# as14120_x31_adc.net
KiCad netlist of a schematic drawn in Altium Designer
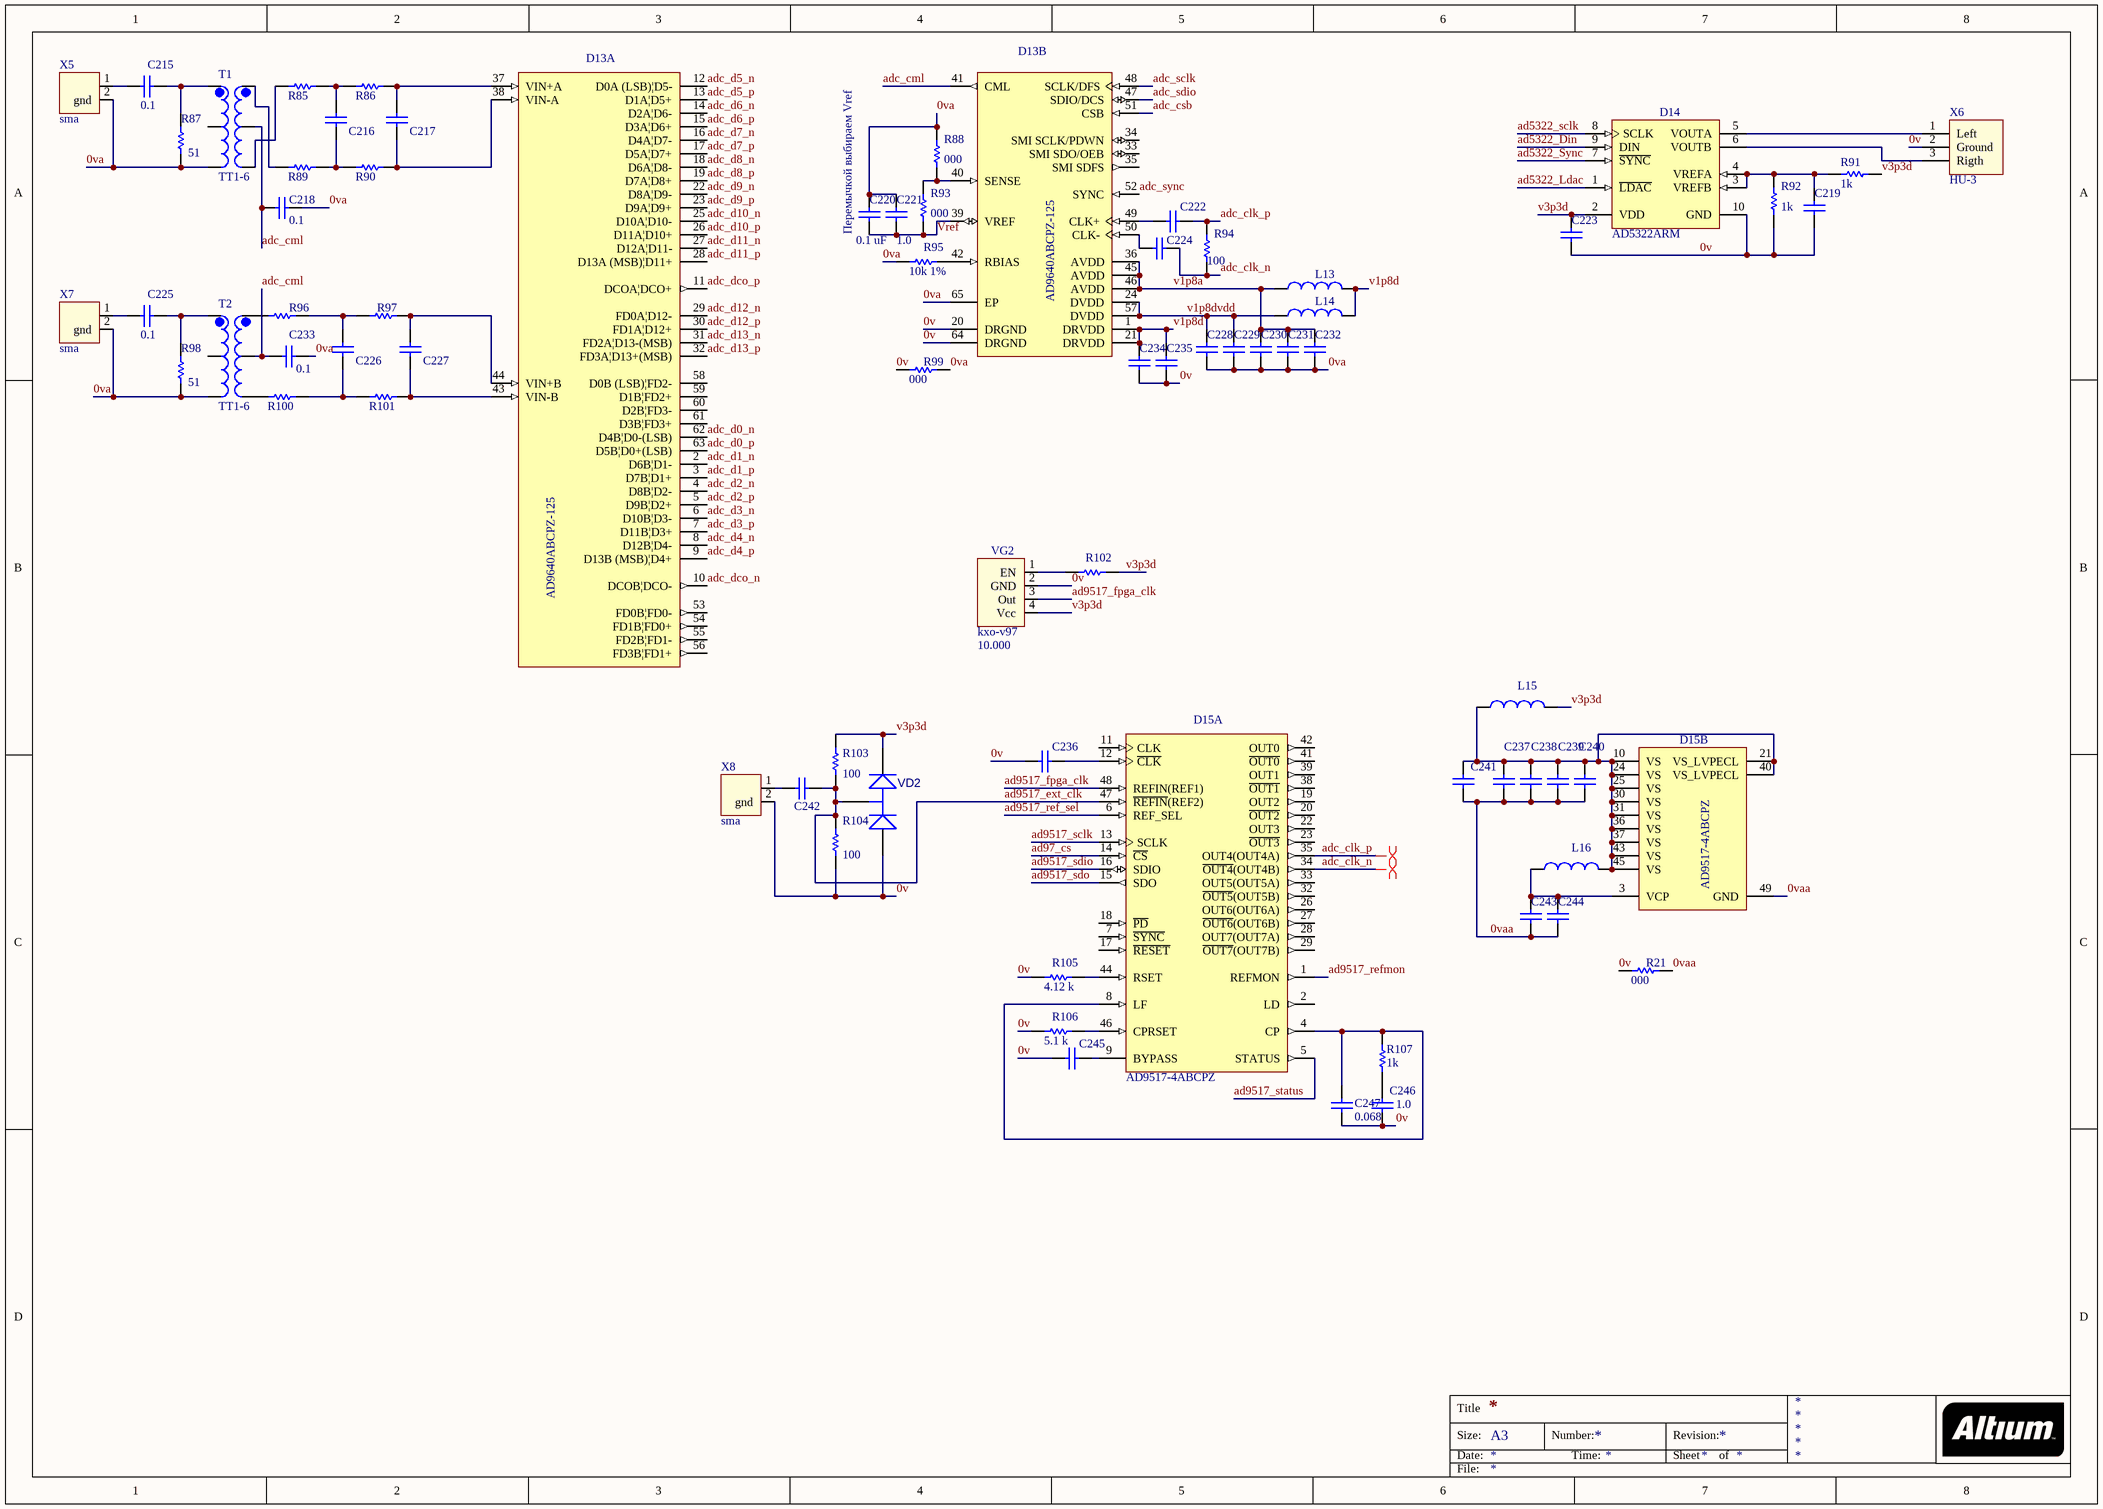
[diagram p0: as14120_x31_adc.SchDoc]

(export (version "E")
  (design (tool "Eeschema 10.0.6"))
  (components
    (comp (ref "C215")
      (value "0.1")
      (footprint "CAPC0402(1005)60_M")
      (description "CAP 1uF 10V ±20% 0402 (1005 Metric) Thickness 0.6mm SMD")
      (fields (field (name "TOLERANCE") "±20%") (field (name "Comment") "CAP 1uF 10V 0402(1005)"))
      (libsource (lib "as14120") (part "CAP_0402"))
    )
    (comp (ref "C216")
      (value "CAP 1uF 10V 0402(1005)")
      (footprint "CAPC0402(1005)60_M")
      (description "CAP 1uF 10V ±20% 0402 (1005 Metric) Thickness 0.6mm SMD")
      (fields (field (name "TOLERANCE") "±20%"))
      (libsource (lib "as14120") (part "CAP_0402"))
    )
    (comp (ref "C217")
      (value "CAP 1uF 10V 0402(1005)")
      (footprint "CAPC0402(1005)60_M")
      (description "CAP 1uF 10V ±20% 0402 (1005 Metric) Thickness 0.6mm SMD")
      (fields (field (name "TOLERANCE") "±20%"))
      (libsource (lib "as14120") (part "CAP_0402"))
    )
    (comp (ref "C218")
      (value "0.1")
      (footprint "CAPC0402(1005)60_M")
      (description "CAP 1uF 10V ±20% 0402 (1005 Metric) Thickness 0.6mm SMD")
      (fields (field (name "TOLERANCE") "±20%") (field (name "Comment") "CAP 1uF 10V 0402(1005)"))
      (libsource (lib "as14120") (part "CAP_0402"))
    )
    (comp (ref "C219")
      (value "CAP 1uF 10V 0402(1005)")
      (footprint "CAPC0402(1005)60_M")
      (description "CAP 1uF 10V ±20% 0402 (1005 Metric) Thickness 0.6mm SMD")
      (fields (field (name "TOLERANCE") "±20%"))
      (libsource (lib "as14120") (part "CAP_0402"))
    )
    (comp (ref "C220")
      (value "0.1 uF")
      (footprint "CAPC0402(1005)60_M")
      (description "CAP 1uF 10V ±20% 0402 (1005 Metric) Thickness 0.6mm SMD")
      (fields (field (name "TOLERANCE") "±20%") (field (name "Comment") "CAP 1uF 10V 0402(1005)"))
      (libsource (lib "as14120") (part "CAP_0402"))
    )
    (comp (ref "C221")
      (value "1.0")
      (footprint "CAPC0402(1005)60_M")
      (description "CAP 1uF 10V ±20% 0402 (1005 Metric) Thickness 0.6mm SMD")
      (fields (field (name "TOLERANCE") "±20%") (field (name "Comment") "CAP 1uF 10V 0402(1005)"))
      (libsource (lib "as14120") (part "CAP_0402"))
    )
    (comp (ref "C222")
      (value "CAP 1uF 10V 0402(1005)")
      (footprint "CAPC0402(1005)60_M")
      (description "CAP 1uF 10V ±20% 0402 (1005 Metric) Thickness 0.6mm SMD")
      (fields (field (name "TOLERANCE") "±20%"))
      (libsource (lib "as14120") (part "CAP_0402"))
    )
    (comp (ref "C223")
      (value "CAP 1uF 10V 0402(1005)")
      (footprint "CAPC0402(1005)60_M")
      (description "CAP 1uF 10V ±20% 0402 (1005 Metric) Thickness 0.6mm SMD")
      (fields (field (name "TOLERANCE") "±20%"))
      (libsource (lib "as14120") (part "CAP_0402"))
    )
    (comp (ref "C224")
      (value "CAP 1uF 10V 0402(1005)")
      (footprint "CAPC0402(1005)60_M")
      (description "CAP 1uF 10V ±20% 0402 (1005 Metric) Thickness 0.6mm SMD")
      (fields (field (name "TOLERANCE") "±20%"))
      (libsource (lib "as14120") (part "CAP_0402"))
    )
    (comp (ref "C225")
      (value "0.1")
      (footprint "CAPC0402(1005)60_M")
      (description "CAP 1uF 10V ±20% 0402 (1005 Metric) Thickness 0.6mm SMD")
      (fields (field (name "TOLERANCE") "±20%") (field (name "Comment") "CAP 1uF 10V 0402(1005)"))
      (libsource (lib "as14120") (part "CAP_0402"))
    )
    (comp (ref "C226")
      (value "CAP 1uF 10V 0402(1005)")
      (footprint "CAPC0402(1005)60_M")
      (description "CAP 1uF 10V ±20% 0402 (1005 Metric) Thickness 0.6mm SMD")
      (fields (field (name "TOLERANCE") "±20%"))
      (libsource (lib "as14120") (part "CAP_0402"))
    )
    (comp (ref "C227")
      (value "CAP 1uF 10V 0402(1005)")
      (footprint "CAPC0402(1005)60_M")
      (description "CAP 1uF 10V ±20% 0402 (1005 Metric) Thickness 0.6mm SMD")
      (fields (field (name "TOLERANCE") "±20%"))
      (libsource (lib "as14120") (part "CAP_0402"))
    )
    (comp (ref "C228")
      (value "CAP 1uF 10V 0402(1005)")
      (footprint "CAPC0402(1005)60_M")
      (description "CAP 1uF 10V ±20% 0402 (1005 Metric) Thickness 0.6mm SMD")
      (fields (field (name "TOLERANCE") "±20%"))
      (libsource (lib "as14120") (part "CAP_0402"))
    )
    (comp (ref "C229")
      (value "CAP 1uF 10V 0402(1005)")
      (footprint "CAPC0402(1005)60_M")
      (description "CAP 1uF 10V ±20% 0402 (1005 Metric) Thickness 0.6mm SMD")
      (fields (field (name "TOLERANCE") "±20%"))
      (libsource (lib "as14120") (part "CAP_0402"))
    )
    (comp (ref "C230")
      (value "CAP 1uF 10V 0402(1005)")
      (footprint "CAPC0402(1005)60_M")
      (description "CAP 1uF 10V ±20% 0402 (1005 Metric) Thickness 0.6mm SMD")
      (fields (field (name "TOLERANCE") "±20%"))
      (libsource (lib "as14120") (part "CAP_0402"))
    )
    (comp (ref "C231")
      (value "CAP 1uF 10V 0402(1005)")
      (footprint "CAPC0402(1005)60_M")
      (description "CAP 1uF 10V ±20% 0402 (1005 Metric) Thickness 0.6mm SMD")
      (fields (field (name "TOLERANCE") "±20%"))
      (libsource (lib "as14120") (part "CAP_0402"))
    )
    (comp (ref "C232")
      (value "CAP 1uF 10V 0402(1005)")
      (footprint "CAPC0402(1005)60_M")
      (description "CAP 1uF 10V ±20% 0402 (1005 Metric) Thickness 0.6mm SMD")
      (fields (field (name "TOLERANCE") "±20%"))
      (libsource (lib "as14120") (part "CAP_0402"))
    )
    (comp (ref "C233")
      (value "0.1")
      (footprint "CAPC0402(1005)60_M")
      (description "CAP 1uF 10V ±20% 0402 (1005 Metric) Thickness 0.6mm SMD")
      (fields (field (name "TOLERANCE") "±20%") (field (name "Comment") "CAP 1uF 10V 0402(1005)"))
      (libsource (lib "as14120") (part "CAP_0402"))
    )
    (comp (ref "C234")
      (value "CAP 1uF 10V 0402(1005)")
      (footprint "CAPC0402(1005)60_M")
      (description "CAP 1uF 10V ±20% 0402 (1005 Metric) Thickness 0.6mm SMD")
      (fields (field (name "TOLERANCE") "±20%"))
      (libsource (lib "as14120") (part "CAP_0402"))
    )
    (comp (ref "C235")
      (value "CAP 1uF 10V 0402(1005)")
      (footprint "CAPC0402(1005)60_M")
      (description "CAP 1uF 10V ±20% 0402 (1005 Metric) Thickness 0.6mm SMD")
      (fields (field (name "TOLERANCE") "±20%"))
      (libsource (lib "as14120") (part "CAP_0402"))
    )
    (comp (ref "C236")
      (value "CAP 1uF 10V 0402(1005)")
      (footprint "CAPC0402(1005)60_M")
      (description "CAP 1uF 10V ±20% 0402 (1005 Metric) Thickness 0.6mm SMD")
      (fields (field (name "TOLERANCE") "±20%"))
      (libsource (lib "as14120") (part "CAP_0402"))
    )
    (comp (ref "C237")
      (value "CAP 1uF 10V 0402(1005)")
      (footprint "CAPC0402(1005)60_M")
      (description "CAP 1uF 10V ±20% 0402 (1005 Metric) Thickness 0.6mm SMD")
      (fields (field (name "TOLERANCE") "±20%"))
      (libsource (lib "as14120") (part "CAP_0402"))
    )
    (comp (ref "C238")
      (value "CAP 1uF 10V 0402(1005)")
      (footprint "CAPC0402(1005)60_M")
      (description "CAP 1uF 10V ±20% 0402 (1005 Metric) Thickness 0.6mm SMD")
      (fields (field (name "TOLERANCE") "±20%"))
      (libsource (lib "as14120") (part "CAP_0402"))
    )
    (comp (ref "C239")
      (value "CAP 1uF 10V 0402(1005)")
      (footprint "CAPC0402(1005)60_M")
      (description "CAP 1uF 10V ±20% 0402 (1005 Metric) Thickness 0.6mm SMD")
      (fields (field (name "TOLERANCE") "±20%"))
      (libsource (lib "as14120") (part "CAP_0402"))
    )
    (comp (ref "C240")
      (value "CAP 1uF 10V 0402(1005)")
      (footprint "CAPC0402(1005)60_M")
      (description "CAP 1uF 10V ±20% 0402 (1005 Metric) Thickness 0.6mm SMD")
      (fields (field (name "TOLERANCE") "±20%"))
      (libsource (lib "as14120") (part "CAP_0402"))
    )
    (comp (ref "C241")
      (value "CAP 1uF 10V 0402(1005)")
      (footprint "CAPC0402(1005)60_M")
      (description "CAP 1uF 10V ±20% 0402 (1005 Metric) Thickness 0.6mm SMD")
      (fields (field (name "TOLERANCE") "±20%"))
      (libsource (lib "as14120") (part "CAP_0402"))
    )
    (comp (ref "C242")
      (value "CAP 1uF 10V 0402(1005)")
      (footprint "CAPC0402(1005)60_M")
      (description "CAP 1uF 10V ±20% 0402 (1005 Metric) Thickness 0.6mm SMD")
      (fields (field (name "TOLERANCE") "±20%"))
      (libsource (lib "as14120") (part "CAP_0402"))
    )
    (comp (ref "C243")
      (value "CAP 1uF 10V 0402(1005)")
      (footprint "CAPC0402(1005)60_M")
      (description "CAP 1uF 10V ±20% 0402 (1005 Metric) Thickness 0.6mm SMD")
      (fields (field (name "TOLERANCE") "±20%"))
      (libsource (lib "as14120") (part "CAP_0402"))
    )
    (comp (ref "C244")
      (value "CAP 1uF 10V 0402(1005)")
      (footprint "CAPC0402(1005)60_M")
      (description "CAP 1uF 10V ±20% 0402 (1005 Metric) Thickness 0.6mm SMD")
      (fields (field (name "TOLERANCE") "±20%"))
      (libsource (lib "as14120") (part "CAP_0402"))
    )
    (comp (ref "C245")
      (value "CAP 1uF 10V 0402(1005)")
      (footprint "CAPC0402(1005)60_M")
      (description "CAP 1uF 10V ±20% 0402 (1005 Metric) Thickness 0.6mm SMD")
      (fields (field (name "TOLERANCE") "±20%"))
      (libsource (lib "as14120") (part "CAP_0402"))
    )
    (comp (ref "C246")
      (value "1.0")
      (footprint "CAPC0805(2012)100_N")
      (fields (field (name "Comment") "CAP_0805"))
      (libsource (lib "as14120") (part "CAP_0805"))
    )
    (comp (ref "C247")
      (value "0.068")
      (footprint "CAPC0805(2012)100_N")
      (fields (field (name "Comment") "CAP_0805"))
      (libsource (lib "as14120") (part "CAP_0805"))
    )
    (comp (ref "D13")
      (value "AD9640ABCPZ-125")
      (footprint "CP-64-6_N")
      (fields (field (name "PART NUMBER") "AD9640-125") (field (name "MANUFACTURER") "Analog Devices"))
      (libsource (lib "Analog Devices Data Converters Analog-to-Digital Converters") (part "AD9640ABCPZ-125"))
    )
    (comp (ref "D14")
      (value "AD5322ARM")
      (footprint "RM-10_L")
      (fields (field (name "ADI PART NUMBER") "AD5322") (field (name "MANUFACTURER") "Analog Devices"))
      (libsource (lib "Analog Devices Data Converters Digital-to-Analog Converters") (part "AD5322ARM"))
    )
    (comp (ref "D15")
      (value "AD9517-4ABCPZ")
      (footprint "ADI-CP-48-8_L")
      (libsource (lib "Analog Devices RF IF Timing ICs and Clocks") (part "AD9517-4ABCPZ"))
    )
    (comp (ref "L13")
      (value "BLM21PG300SN1D")
      (footprint "CAPC0805(2012)100_N")
      (libsource (lib "as14120") (part "Ferrite_beat"))
    )
    (comp (ref "L14")
      (value "BLM21PG300SN1D")
      (footprint "CAPC0805(2012)100_N")
      (libsource (lib "as14120") (part "Ferrite_beat"))
    )
    (comp (ref "L15")
      (value "BLM21PG300SN1D")
      (footprint "CAPC0805(2012)100_N")
      (libsource (lib "as14120") (part "Ferrite_beat"))
    )
    (comp (ref "L16")
      (value "BLM21PG300SN1D")
      (footprint "CAPC0805(2012)100_N")
      (libsource (lib "as14120") (part "Ferrite_beat"))
    )
    (comp (ref "R21")
      (value "000")
      (footprint "RESC0603(1608)_L")
      (description "1K 0.1W 5% 0603 (1608 Metric)  SMD")
      (fields (field (name "TOLERANCE") "5 %") (field (name "POWER") "0.1 W"))
      (libsource (lib "as14120") (part "RES_0603"))
    )
    (comp (ref "R85")
      (value "1K 5% 0603(1608)")
      (footprint "RESC0603(1608)_L")
      (description "1K 0.1W 5% 0603 (1608 Metric)  SMD")
      (fields (field (name "TOLERANCE") "5 %") (field (name "POWER") "0.1 W"))
      (libsource (lib "as14120") (part "RES_0603"))
    )
    (comp (ref "R86")
      (value "1K 5% 0603(1608)")
      (footprint "RESC0603(1608)_L")
      (description "1K 0.1W 5% 0603 (1608 Metric)  SMD")
      (fields (field (name "TOLERANCE") "5 %") (field (name "POWER") "0.1 W"))
      (libsource (lib "as14120") (part "RES_0603"))
    )
    (comp (ref "R87")
      (value "51")
      (footprint "RESC0805(2012)_L")
      (description "1K 0.125W 1% 0805 (2012 Metric)  SMD")
      (fields (field (name "TOLERANCE") "1 %") (field (name "POWER") "0.125 W"))
      (libsource (lib "as14120") (part "RES_0805"))
    )
    (comp (ref "R88")
      (value "000")
      (footprint "RESC0603(1608)_L")
      (description "1K 0.1W 5% 0603 (1608 Metric)  SMD")
      (fields (field (name "TOLERANCE") "5 %") (field (name "POWER") "0.1 W"))
      (libsource (lib "as14120") (part "RES_0603"))
    )
    (comp (ref "R89")
      (value "1K 5% 0603(1608)")
      (footprint "RESC0603(1608)_L")
      (description "1K 0.1W 5% 0603 (1608 Metric)  SMD")
      (fields (field (name "TOLERANCE") "5 %") (field (name "POWER") "0.1 W"))
      (libsource (lib "as14120") (part "RES_0603"))
    )
    (comp (ref "R90")
      (value "1K 5% 0603(1608)")
      (footprint "RESC0603(1608)_L")
      (description "1K 0.1W 5% 0603 (1608 Metric)  SMD")
      (fields (field (name "TOLERANCE") "5 %") (field (name "POWER") "0.1 W"))
      (libsource (lib "as14120") (part "RES_0603"))
    )
    (comp (ref "R91")
      (value "1k")
      (footprint "RESC0603(1608)_L")
      (description "1K 0.1W 5% 0603 (1608 Metric)  SMD")
      (fields (field (name "TOLERANCE") "5 %") (field (name "POWER") "0.1 W"))
      (libsource (lib "as14120") (part "RES_0603"))
    )
    (comp (ref "R92")
      (value "1k")
      (footprint "RESC0603(1608)_L")
      (description "1K 0.1W 5% 0603 (1608 Metric)  SMD")
      (fields (field (name "TOLERANCE") "5 %") (field (name "POWER") "0.1 W"))
      (libsource (lib "as14120") (part "RES_0603"))
    )
    (comp (ref "R93")
      (value "000")
      (footprint "RESC0603(1608)_L")
      (description "1K 0.1W 5% 0603 (1608 Metric)  SMD")
      (fields (field (name "TOLERANCE") "5 %") (field (name "POWER") "0.1 W"))
      (libsource (lib "as14120") (part "RES_0603"))
    )
    (comp (ref "R94")
      (value "100")
      (footprint "RESC0805(2012)_L")
      (description "1K 0.125W 1% 0805 (2012 Metric)  SMD")
      (fields (field (name "TOLERANCE") "1 %") (field (name "POWER") "0.125 W"))
      (libsource (lib "as14120") (part "RES_0805"))
    )
    (comp (ref "R95")
      (value "10k 1%")
      (footprint "RESC0805(2012)_L")
      (description "1K 0.125W 1% 0805 (2012 Metric)  SMD")
      (fields (field (name "TOLERANCE") "1 %") (field (name "POWER") "0.125 W"))
      (libsource (lib "as14120") (part "RES_0805"))
    )
    (comp (ref "R96")
      (value "1K 5% 0603(1608)")
      (footprint "RESC0603(1608)_L")
      (description "1K 0.1W 5% 0603 (1608 Metric)  SMD")
      (fields (field (name "TOLERANCE") "5 %") (field (name "POWER") "0.1 W"))
      (libsource (lib "as14120") (part "RES_0603"))
    )
    (comp (ref "R97")
      (value "1K 5% 0603(1608)")
      (footprint "RESC0603(1608)_L")
      (description "1K 0.1W 5% 0603 (1608 Metric)  SMD")
      (fields (field (name "TOLERANCE") "5 %") (field (name "POWER") "0.1 W"))
      (libsource (lib "as14120") (part "RES_0603"))
    )
    (comp (ref "R98")
      (value "51")
      (footprint "RESC0805(2012)_L")
      (description "1K 0.125W 1% 0805 (2012 Metric)  SMD")
      (fields (field (name "TOLERANCE") "1 %") (field (name "POWER") "0.125 W"))
      (libsource (lib "as14120") (part "RES_0805"))
    )
    (comp (ref "R99")
      (value "000")
      (footprint "RESC0603(1608)_L")
      (description "1K 0.1W 5% 0603 (1608 Metric)  SMD")
      (fields (field (name "TOLERANCE") "5 %") (field (name "POWER") "0.1 W"))
      (libsource (lib "as14120") (part "RES_0603"))
    )
    (comp (ref "R100")
      (value "1K 5% 0603(1608)")
      (footprint "RESC0603(1608)_L")
      (description "1K 0.1W 5% 0603 (1608 Metric)  SMD")
      (fields (field (name "TOLERANCE") "5 %") (field (name "POWER") "0.1 W"))
      (libsource (lib "as14120") (part "RES_0603"))
    )
    (comp (ref "R101")
      (value "1K 5% 0603(1608)")
      (footprint "RESC0603(1608)_L")
      (description "1K 0.1W 5% 0603 (1608 Metric)  SMD")
      (fields (field (name "TOLERANCE") "5 %") (field (name "POWER") "0.1 W"))
      (libsource (lib "as14120") (part "RES_0603"))
    )
    (comp (ref "R102")
      (value "1K 5% 0603(1608)")
      (footprint "RESC0603(1608)_L")
      (description "1K 0.1W 5% 0603 (1608 Metric)  SMD")
      (fields (field (name "TOLERANCE") "5 %") (field (name "POWER") "0.1 W"))
      (libsource (lib "as14120") (part "RES_0603"))
    )
    (comp (ref "R103")
      (value "100")
      (footprint "RESC0805(2012)_L")
      (description "1K 0.125W 1% 0805 (2012 Metric)  SMD")
      (fields (field (name "TOLERANCE") "1 %") (field (name "POWER") "0.125 W"))
      (libsource (lib "as14120") (part "RES_0805"))
    )
    (comp (ref "R104")
      (value "100")
      (footprint "RESC0805(2012)_L")
      (description "1K 0.125W 1% 0805 (2012 Metric)  SMD")
      (fields (field (name "TOLERANCE") "1 %") (field (name "POWER") "0.125 W"))
      (libsource (lib "as14120") (part "RES_0805"))
    )
    (comp (ref "R105")
      (value "4.12 k")
      (footprint "RESC0805(2012)_L")
      (description "1K 0.125W 1% 0805 (2012 Metric)  SMD")
      (fields (field (name "TOLERANCE") "1 %") (field (name "POWER") "0.125 W"))
      (libsource (lib "as14120") (part "RES_0805"))
    )
    (comp (ref "R106")
      (value "5.1 k")
      (footprint "RESC0805(2012)_L")
      (description "1K 0.125W 1% 0805 (2012 Metric)  SMD")
      (fields (field (name "TOLERANCE") "1 %") (field (name "POWER") "0.125 W"))
      (libsource (lib "as14120") (part "RES_0805"))
    )
    (comp (ref "R107")
      (value "1k")
      (footprint "RESC0805(2012)_L")
      (description "1K 0.125W 1% 0805 (2012 Metric)  SMD")
      (fields (field (name "TOLERANCE") "1 %") (field (name "POWER") "0.125 W"))
      (libsource (lib "as14120") (part "RES_0805"))
    )
    (comp (ref "T1") (value "TT1-6") (footprint "TT!-6-KK81") (libsource (lib "as14120") (part "TT1-6-KK81")))
    (comp (ref "T2") (value "TT1-6") (footprint "TT!-6-KK81") (libsource (lib "as14120") (part "TT1-6-KK81")))
    (comp (ref "VD2")
      (value "BAV99")
      (footprint "SO-G3/X.9")
      (description "SOT23 Silicon Planar High-Speed Switching Series Diode Pair")
      (libsource (lib "alexsb") (part "BAV99"))
    )
    (comp (ref "VG2")
      (value "kxo-v97")
      (footprint "kxo-v97")
      (fields (field (name "ALTIUM_VALUE") "10.000"))
      (libsource (lib "as14120") (part "kxo-v97"))
    )
    (comp (ref "X5") (value "sma") (footprint "sma") (libsource (lib "as14120") (part "sma")))
    (comp (ref "X6") (value "HU-3") (footprint "HU-3") (libsource (lib "as14120") (part "HU-3")))
    (comp (ref "X7") (value "sma") (footprint "sma") (libsource (lib "as14120") (part "sma")))
    (comp (ref "X8") (value "sma") (footprint "sma") (libsource (lib "as14120") (part "sma")))
  )
  (nets
    (net (code "1") (name "/0v") (class "Default")
      (node (ref "C219") (pin "1") (pinfunction "1_1") (pintype "passive"))
      (node (ref "C223") (pin "1") (pinfunction "1_1") (pintype "passive"))
      (node (ref "C234") (pin "1") (pinfunction "1_1") (pintype "passive"))
      (node (ref "C235") (pin "1") (pinfunction "1_1") (pintype "passive"))
      (node (ref "C236") (pin "1") (pinfunction "1_1") (pintype "passive"))
      (node (ref "C245") (pin "1") (pinfunction "1_1") (pintype "passive"))
      (node (ref "C246") (pin "1") (pinfunction "1_1") (pintype "passive"))
      (node (ref "C247") (pin "1") (pinfunction "1_1") (pintype "passive"))
      (node (ref "D13") (pin "20") (pinfunction "DRGND_20") (pintype "power_in"))
      (node (ref "D13") (pin "64") (pinfunction "DRGND_64") (pintype "power_in"))
      (node (ref "D14") (pin "10") (pinfunction "GND_10") (pintype "power_in"))
      (node (ref "R104") (pin "1") (pinfunction "1_1") (pintype "passive"))
      (node (ref "R105") (pin "2") (pinfunction "2_2") (pintype "passive"))
      (node (ref "R106") (pin "2") (pinfunction "2_2") (pintype "passive"))
      (node (ref "R21") (pin "1") (pinfunction "1_1") (pintype "passive"))
      (node (ref "R92") (pin "2") (pinfunction "2_2") (pintype "passive"))
      (node (ref "R99") (pin "1") (pinfunction "1_1") (pintype "passive"))
      (node (ref "VD2") (pin "3") (pinfunction "A_3") (pintype "passive"))
      (node (ref "VG2") (pin "2") (pinfunction "GND_2") (pintype "passive"))
      (node (ref "X6") (pin "2") (pinfunction "Ground_2") (pintype "passive"))
      (node (ref "X8") (pin "2") (pinfunction "gnd_2") (pintype "passive"))
    )
    (net (code "2") (name "/0va") (class "Default")
      (node (ref "C218") (pin "2") (pinfunction "2_2") (pintype "passive"))
      (node (ref "C220") (pin "2") (pinfunction "2_2") (pintype "passive"))
      (node (ref "C221") (pin "2") (pinfunction "2_2") (pintype "passive"))
      (node (ref "C228") (pin "1") (pinfunction "1_1") (pintype "passive"))
      (node (ref "C229") (pin "1") (pinfunction "1_1") (pintype "passive"))
      (node (ref "C230") (pin "1") (pinfunction "1_1") (pintype "passive"))
      (node (ref "C231") (pin "1") (pinfunction "1_1") (pintype "passive"))
      (node (ref "C232") (pin "1") (pinfunction "1_1") (pintype "passive"))
      (node (ref "C233") (pin "2") (pinfunction "2_2") (pintype "passive"))
      (node (ref "D13") (pin "65") (pinfunction "EP_65") (pintype "power_in"))
      (node (ref "R87") (pin "1") (pinfunction "1_1") (pintype "passive"))
      (node (ref "R88") (pin "1") (pinfunction "1_1") (pintype "passive"))
      (node (ref "R95") (pin "2") (pinfunction "2_2") (pintype "passive"))
      (node (ref "R98") (pin "1") (pinfunction "1_1") (pintype "passive"))
      (node (ref "R99") (pin "2") (pinfunction "2_2") (pintype "passive"))
      (node (ref "T1") (pin "6") (pinfunction "6_6") (pintype "passive"))
      (node (ref "T2") (pin "6") (pinfunction "6_6") (pintype "passive"))
      (node (ref "X5") (pin "2") (pinfunction "gnd_2") (pintype "passive"))
      (node (ref "X7") (pin "2") (pinfunction "gnd_2") (pintype "passive"))
    )
    (net (code "3") (name "/0vaa") (class "Default")
      (node (ref "C237") (pin "1") (pinfunction "1_1") (pintype "passive"))
      (node (ref "C238") (pin "1") (pinfunction "1_1") (pintype "passive"))
      (node (ref "C239") (pin "1") (pinfunction "1_1") (pintype "passive"))
      (node (ref "C240") (pin "1") (pinfunction "1_1") (pintype "passive"))
      (node (ref "C241") (pin "1") (pinfunction "1_1") (pintype "passive"))
      (node (ref "C243") (pin "1") (pinfunction "1_1") (pintype "passive"))
      (node (ref "C244") (pin "1") (pinfunction "1_1") (pintype "passive"))
      (node (ref "D15") (pin "49") (pinfunction "GND_49") (pintype "power_in"))
      (node (ref "R21") (pin "2") (pinfunction "2_2") (pintype "passive"))
    )
    (net (code "4") (name "/Vref") (class "Default")
      (node (ref "C220") (pin "1") (pinfunction "1_1") (pintype "passive"))
      (node (ref "C221") (pin "1") (pinfunction "1_1") (pintype "passive"))
      (node (ref "D13") (pin "39") (pinfunction "VREF_39") (pintype "bidirectional"))
      (node (ref "R93") (pin "2") (pinfunction "2_2") (pintype "passive"))
    )
    (net (code "5") (name "/ad97_cs") (class "Default")
      (node (ref "D15") (pin "14") (pinfunction "~{CS}_14") (pintype "input"))
    )
    (net (code "6") (name "/ad5322_Din") (class "Default")
      (node (ref "D14") (pin "9") (pinfunction "DIN_9") (pintype "input"))
    )
    (net (code "7") (name "/ad5322_Ldac") (class "Default")
      (node (ref "D14") (pin "1") (pinfunction "~{LDAC}_1") (pintype "input"))
    )
    (net (code "8") (name "/ad5322_Sync") (class "Default")
      (node (ref "D14") (pin "7") (pinfunction "~{SYNC}_7") (pintype "input"))
    )
    (net (code "9") (name "/ad5322_sclk") (class "Default")
      (node (ref "D14") (pin "8") (pinfunction "SCLK_8") (pintype "input"))
    )
    (net (code "10") (name "/ad9517_ext_clk") (class "Default")
      (node (ref "C242") (pin "2") (pinfunction "2_2") (pintype "passive"))
      (node (ref "D15") (pin "47") (pinfunction "~{REFIN}(REF2)_47") (pintype "input"))
      (node (ref "R103") (pin "1") (pinfunction "1_1") (pintype "passive"))
      (node (ref "R104") (pin "2") (pinfunction "2_2") (pintype "passive"))
      (node (ref "VD2") (pin "1") (pinfunction "C_1") (pintype "passive"))
    )
    (net (code "11") (name "/ad9517_fpga_clk") (class "Default")
      (node (ref "D15") (pin "48") (pinfunction "REFIN(REF1)_48") (pintype "input"))
      (node (ref "VG2") (pin "3") (pinfunction "Out_3") (pintype "passive"))
    )
    (net (code "12") (name "/ad9517_ref_sel") (class "Default")
      (node (ref "D15") (pin "6") (pinfunction "REF_SEL_6") (pintype "input"))
    )
    (net (code "13") (name "/ad9517_refmon") (class "Default")
      (node (ref "D15") (pin "1") (pinfunction "REFMON_1") (pintype "output"))
    )
    (net (code "14") (name "/ad9517_sclk") (class "Default")
      (node (ref "D15") (pin "13") (pinfunction "SCLK_13") (pintype "input"))
    )
    (net (code "15") (name "/ad9517_sdio") (class "Default")
      (node (ref "D15") (pin "16") (pinfunction "SDIO_16") (pintype "bidirectional"))
    )
    (net (code "16") (name "/ad9517_sdo") (class "Default")
      (node (ref "D15") (pin "15") (pinfunction "SDO_15") (pintype "output"))
    )
    (net (code "17") (name "/ad9517_status") (class "Default")
      (node (ref "D15") (pin "5") (pinfunction "STATUS_5") (pintype "output"))
    )
    (net (code "18") (name "/adc_clk_n") (class "Default")
      (node (ref "C224") (pin "1") (pinfunction "1_1") (pintype "passive"))
      (node (ref "D15") (pin "34") (pinfunction "~{OUT4}(OUT4B)_34") (pintype "output"))
      (node (ref "R94") (pin "1") (pinfunction "1_1") (pintype "passive"))
    )
    (net (code "19") (name "/adc_clk_p") (class "Default")
      (node (ref "C222") (pin "1") (pinfunction "1_1") (pintype "passive"))
      (node (ref "D15") (pin "35") (pinfunction "OUT4(OUT4A)_35") (pintype "output"))
      (node (ref "R94") (pin "2") (pinfunction "2_2") (pintype "passive"))
    )
    (net (code "20") (name "/adc_cml") (class "Default")
      (node (ref "C218") (pin "1") (pinfunction "1_1") (pintype "passive"))
      (node (ref "C233") (pin "1") (pinfunction "1_1") (pintype "passive"))
      (node (ref "D13") (pin "41") (pinfunction "CML_41") (pintype "output"))
      (node (ref "T1") (pin "2") (pinfunction "2_2") (pintype "passive"))
      (node (ref "T2") (pin "2") (pinfunction "2_2") (pintype "passive"))
    )
    (net (code "21") (name "/adc_csb") (class "Default")
      (node (ref "D13") (pin "51") (pinfunction "CSB_51") (pintype "input"))
    )
    (net (code "22") (name "/adc_d0_n") (class "Default")
      (node (ref "D13") (pin "62") (pinfunction "D4B¦D0-(LSB)_62") (pintype "tri_state"))
    )
    (net (code "23") (name "/adc_d0_p") (class "Default")
      (node (ref "D13") (pin "63") (pinfunction "D5B¦D0+(LSB)_63") (pintype "tri_state"))
    )
    (net (code "24") (name "/adc_d1_n") (class "Default")
      (node (ref "D13") (pin "2") (pinfunction "D6B¦D1-_2") (pintype "tri_state"))
    )
    (net (code "25") (name "/adc_d1_p") (class "Default")
      (node (ref "D13") (pin "3") (pinfunction "D7B¦D1+_3") (pintype "tri_state"))
    )
    (net (code "26") (name "/adc_d2_n") (class "Default")
      (node (ref "D13") (pin "4") (pinfunction "D8B¦D2-_4") (pintype "tri_state"))
    )
    (net (code "27") (name "/adc_d2_p") (class "Default")
      (node (ref "D13") (pin "5") (pinfunction "D9B¦D2+_5") (pintype "tri_state"))
    )
    (net (code "28") (name "/adc_d3_n") (class "Default")
      (node (ref "D13") (pin "6") (pinfunction "D10B¦D3-_6") (pintype "tri_state"))
    )
    (net (code "29") (name "/adc_d3_p") (class "Default")
      (node (ref "D13") (pin "7") (pinfunction "D11B¦D3+_7") (pintype "tri_state"))
    )
    (net (code "30") (name "/adc_d4_n") (class "Default")
      (node (ref "D13") (pin "8") (pinfunction "D12B¦D4-_8") (pintype "tri_state"))
    )
    (net (code "31") (name "/adc_d4_p") (class "Default")
      (node (ref "D13") (pin "9") (pinfunction "D13B_(MSB)¦D4+_9") (pintype "tri_state"))
    )
    (net (code "32") (name "/adc_d5_n") (class "Default")
      (node (ref "D13") (pin "12") (pinfunction "D0A_(LSB)¦D5-_12") (pintype "tri_state"))
    )
    (net (code "33") (name "/adc_d5_p") (class "Default")
      (node (ref "D13") (pin "13") (pinfunction "D1A¦D5+_13") (pintype "tri_state"))
    )
    (net (code "34") (name "/adc_d6_n") (class "Default")
      (node (ref "D13") (pin "14") (pinfunction "D2A¦D6-_14") (pintype "tri_state"))
    )
    (net (code "35") (name "/adc_d6_p") (class "Default")
      (node (ref "D13") (pin "15") (pinfunction "D3A¦D6+_15") (pintype "tri_state"))
    )
    (net (code "36") (name "/adc_d7_n") (class "Default")
      (node (ref "D13") (pin "16") (pinfunction "D4A¦D7-_16") (pintype "tri_state"))
    )
    (net (code "37") (name "/adc_d7_p") (class "Default")
      (node (ref "D13") (pin "17") (pinfunction "D5A¦D7+_17") (pintype "tri_state"))
    )
    (net (code "38") (name "/adc_d8_n") (class "Default")
      (node (ref "D13") (pin "18") (pinfunction "D6A¦D8-_18") (pintype "tri_state"))
    )
    (net (code "39") (name "/adc_d8_p") (class "Default")
      (node (ref "D13") (pin "19") (pinfunction "D7A¦D8+_19") (pintype "tri_state"))
    )
    (net (code "40") (name "/adc_d9_n") (class "Default")
      (node (ref "D13") (pin "22") (pinfunction "D8A¦D9-_22") (pintype "tri_state"))
    )
    (net (code "41") (name "/adc_d9_p") (class "Default")
      (node (ref "D13") (pin "23") (pinfunction "D9A¦D9+_23") (pintype "tri_state"))
    )
    (net (code "42") (name "/adc_d10_n") (class "Default")
      (node (ref "D13") (pin "25") (pinfunction "D10A¦D10-_25") (pintype "tri_state"))
    )
    (net (code "43") (name "/adc_d10_p") (class "Default")
      (node (ref "D13") (pin "26") (pinfunction "D11A¦D10+_26") (pintype "tri_state"))
    )
    (net (code "44") (name "/adc_d11_n") (class "Default")
      (node (ref "D13") (pin "27") (pinfunction "D12A¦D11-_27") (pintype "tri_state"))
    )
    (net (code "45") (name "/adc_d11_p") (class "Default")
      (node (ref "D13") (pin "28") (pinfunction "D13A_(MSB)¦D11+_28") (pintype "tri_state"))
    )
    (net (code "46") (name "/adc_d12_n") (class "Default")
      (node (ref "D13") (pin "29") (pinfunction "FD0A¦D12-_29") (pintype "tri_state"))
    )
    (net (code "47") (name "/adc_d12_p") (class "Default")
      (node (ref "D13") (pin "30") (pinfunction "FD1A¦D12+_30") (pintype "tri_state"))
    )
    (net (code "48") (name "/adc_d13_n") (class "Default")
      (node (ref "D13") (pin "31") (pinfunction "FD2A¦D13-(MSB)_31") (pintype "tri_state"))
    )
    (net (code "49") (name "/adc_d13_p") (class "Default")
      (node (ref "D13") (pin "32") (pinfunction "FD3A¦D13+(MSB)_32") (pintype "tri_state"))
    )
    (net (code "50") (name "/adc_dco_n") (class "Default")
      (node (ref "D13") (pin "10") (pinfunction "DCOB¦DCO-_10") (pintype "output"))
    )
    (net (code "51") (name "/adc_dco_p") (class "Default")
      (node (ref "D13") (pin "11") (pinfunction "DCOA¦DCO+_11") (pintype "output"))
    )
    (net (code "52") (name "/adc_sclk") (class "Default")
      (node (ref "D13") (pin "48") (pinfunction "SCLK/DFS_48") (pintype "input"))
    )
    (net (code "53") (name "/adc_sdio") (class "Default")
      (node (ref "D13") (pin "47") (pinfunction "SDIO/DCS_47") (pintype "bidirectional"))
    )
    (net (code "54") (name "/adc_sync") (class "Default")
      (node (ref "D13") (pin "52") (pinfunction "SYNC_52") (pintype "input"))
    )
    (net (code "55") (name "/v1p8a") (class "Default")
      (node (ref "C230") (pin "2") (pinfunction "2_2") (pintype "passive"))
      (node (ref "C231") (pin "2") (pinfunction "2_2") (pintype "passive"))
      (node (ref "C232") (pin "2") (pinfunction "2_2") (pintype "passive"))
      (node (ref "D13") (pin "36") (pinfunction "AVDD_36") (pintype "power_in"))
      (node (ref "D13") (pin "45") (pinfunction "AVDD_45") (pintype "power_in"))
      (node (ref "D13") (pin "46") (pinfunction "AVDD_46") (pintype "power_in"))
      (node (ref "L13") (pin "1") (pinfunction "1_1") (pintype "passive"))
    )
    (net (code "56") (name "/v1p8d") (class "Default")
      (node (ref "C234") (pin "2") (pinfunction "2_2") (pintype "passive"))
      (node (ref "C235") (pin "2") (pinfunction "2_2") (pintype "passive"))
      (node (ref "D13") (pin "1") (pinfunction "DRVDD_1") (pintype "power_in"))
      (node (ref "D13") (pin "21") (pinfunction "DRVDD_21") (pintype "power_in"))
      (node (ref "L13") (pin "2") (pinfunction "2_2") (pintype "passive"))
      (node (ref "L14") (pin "2") (pinfunction "2_2") (pintype "passive"))
    )
    (net (code "57") (name "/v1p8dvdd") (class "Default")
      (node (ref "C228") (pin "2") (pinfunction "2_2") (pintype "passive"))
      (node (ref "C229") (pin "2") (pinfunction "2_2") (pintype "passive"))
      (node (ref "D13") (pin "24") (pinfunction "DVDD_24") (pintype "power_in"))
      (node (ref "D13") (pin "57") (pinfunction "DVDD_57") (pintype "power_in"))
      (node (ref "L14") (pin "1") (pinfunction "1_1") (pintype "passive"))
    )
    (net (code "58") (name "/v3p3d") (class "Default")
      (node (ref "C223") (pin "2") (pinfunction "2_2") (pintype "passive"))
      (node (ref "D14") (pin "2") (pinfunction "VDD_2") (pintype "power_in"))
      (node (ref "L15") (pin "2") (pinfunction "2_2") (pintype "passive"))
      (node (ref "R102") (pin "1") (pinfunction "1_1") (pintype "passive"))
      (node (ref "R103") (pin "2") (pinfunction "2_2") (pintype "passive"))
      (node (ref "R91") (pin "2") (pinfunction "2_2") (pintype "passive"))
      (node (ref "VD2") (pin "2") (pinfunction "K_2") (pintype "passive"))
      (node (ref "VG2") (pin "4") (pinfunction "Vcc_4") (pintype "passive"))
    )
    (net (code "59") (name "Net-(C215-Pad1)") (class "Default")
      (node (ref "C215") (pin "1") (pinfunction "1_1") (pintype "passive"))
      (node (ref "X5") (pin "1") (pintype "passive"))
    )
    (net (code "60") (name "Net-(C215-Pad2)") (class "Default")
      (node (ref "C215") (pin "2") (pinfunction "2_2") (pintype "passive"))
      (node (ref "R87") (pin "2") (pinfunction "2_2") (pintype "passive"))
      (node (ref "T1") (pin "4") (pinfunction "4_4") (pintype "passive"))
    )
    (net (code "61") (name "Net-(C216-Pad1)") (class "Default")
      (node (ref "C216") (pin "1") (pinfunction "1_1") (pintype "passive"))
      (node (ref "R89") (pin "1") (pinfunction "1_1") (pintype "passive"))
      (node (ref "R90") (pin "2") (pinfunction "2_2") (pintype "passive"))
    )
    (net (code "62") (name "Net-(C216-Pad2)") (class "Default")
      (node (ref "C216") (pin "2") (pinfunction "2_2") (pintype "passive"))
      (node (ref "R85") (pin "1") (pinfunction "1_1") (pintype "passive"))
      (node (ref "R86") (pin "2") (pinfunction "2_2") (pintype "passive"))
    )
    (net (code "63") (name "Net-(C225-Pad1)") (class "Default")
      (node (ref "C225") (pin "1") (pinfunction "1_1") (pintype "passive"))
      (node (ref "X7") (pin "1") (pintype "passive"))
    )
    (net (code "64") (name "Net-(C225-Pad2)") (class "Default")
      (node (ref "C225") (pin "2") (pinfunction "2_2") (pintype "passive"))
      (node (ref "R98") (pin "2") (pinfunction "2_2") (pintype "passive"))
      (node (ref "T2") (pin "4") (pinfunction "4_4") (pintype "passive"))
    )
    (net (code "65") (name "Net-(C226-Pad1)") (class "Default")
      (node (ref "C226") (pin "1") (pinfunction "1_1") (pintype "passive"))
      (node (ref "R100") (pin "1") (pinfunction "1_1") (pintype "passive"))
      (node (ref "R101") (pin "2") (pinfunction "2_2") (pintype "passive"))
    )
    (net (code "66") (name "Net-(C226-Pad2)") (class "Default")
      (node (ref "C226") (pin "2") (pinfunction "2_2") (pintype "passive"))
      (node (ref "R96") (pin "1") (pinfunction "1_1") (pintype "passive"))
      (node (ref "R97") (pin "2") (pinfunction "2_2") (pintype "passive"))
    )
    (net (code "67") (name "Net-(C237-Pad2)") (class "Default")
      (node (ref "C237") (pin "2") (pinfunction "2_2") (pintype "passive"))
      (node (ref "C238") (pin "2") (pinfunction "2_2") (pintype "passive"))
      (node (ref "C239") (pin "2") (pinfunction "2_2") (pintype "passive"))
      (node (ref "C240") (pin "2") (pinfunction "2_2") (pintype "passive"))
      (node (ref "C241") (pin "2") (pinfunction "2_2") (pintype "passive"))
      (node (ref "D15") (pin "10") (pinfunction "VS_10") (pintype "power_in"))
      (node (ref "D15") (pin "21") (pinfunction "VS_LVPECL_21") (pintype "power_in"))
      (node (ref "D15") (pin "24") (pinfunction "VS_24") (pintype "power_in"))
      (node (ref "D15") (pin "25") (pinfunction "VS_25") (pintype "power_in"))
      (node (ref "D15") (pin "30") (pinfunction "VS_30") (pintype "power_in"))
      (node (ref "D15") (pin "31") (pinfunction "VS_31") (pintype "power_in"))
      (node (ref "D15") (pin "36") (pinfunction "VS_36") (pintype "power_in"))
      (node (ref "D15") (pin "37") (pinfunction "VS_37") (pintype "power_in"))
      (node (ref "D15") (pin "40") (pinfunction "VS_LVPECL_40") (pintype "power_in"))
      (node (ref "D15") (pin "43") (pinfunction "VS_43") (pintype "power_in"))
      (node (ref "D15") (pin "45") (pinfunction "VS_45") (pintype "power_in"))
      (node (ref "L15") (pin "1") (pinfunction "1_1") (pintype "passive"))
      (node (ref "L16") (pin "2") (pinfunction "2_2") (pintype "passive"))
    )
    (net (code "68") (name "Net-(C242-Pad1)") (class "Default")
      (node (ref "C242") (pin "1") (pinfunction "1_1") (pintype "passive"))
      (node (ref "X8") (pin "1") (pintype "passive"))
    )
    (net (code "69") (name "Net-(C246-Pad2)") (class "Default")
      (node (ref "C246") (pin "2") (pinfunction "2_2") (pintype "passive"))
      (node (ref "R107") (pin "2") (pinfunction "2_2") (pintype "passive"))
    )
    (net (code "70") (name "Net-(D13A-VIN+A)") (class "Default")
      (node (ref "C217") (pin "2") (pinfunction "2_2") (pintype "passive"))
      (node (ref "D13") (pin "37") (pinfunction "VIN+A_37") (pintype "input"))
      (node (ref "R86") (pin "1") (pinfunction "1_1") (pintype "passive"))
    )
    (net (code "71") (name "Net-(D13A-VIN+B)") (class "Default")
      (node (ref "C227") (pin "2") (pinfunction "2_2") (pintype "passive"))
      (node (ref "D13") (pin "44") (pinfunction "VIN+B_44") (pintype "input"))
      (node (ref "R97") (pin "1") (pinfunction "1_1") (pintype "passive"))
    )
    (net (code "72") (name "Net-(D13A-VIN-A)") (class "Default")
      (node (ref "C217") (pin "1") (pinfunction "1_1") (pintype "passive"))
      (node (ref "D13") (pin "38") (pinfunction "VIN-A_38") (pintype "input"))
      (node (ref "R90") (pin "1") (pinfunction "1_1") (pintype "passive"))
    )
    (net (code "73") (name "Net-(D13A-VIN-B)") (class "Default")
      (node (ref "C227") (pin "1") (pinfunction "1_1") (pintype "passive"))
      (node (ref "D13") (pin "43") (pinfunction "VIN-B_43") (pintype "input"))
      (node (ref "R101") (pin "1") (pinfunction "1_1") (pintype "passive"))
    )
    (net (code "74") (name "Net-(D13B-CLK+)") (class "Default")
      (node (ref "C222") (pin "2") (pinfunction "2_2") (pintype "passive"))
      (node (ref "D13") (pin "49") (pinfunction "CLK+_49") (pintype "input"))
    )
    (net (code "75") (name "Net-(D13B-CLK-)") (class "Default")
      (node (ref "C224") (pin "2") (pinfunction "2_2") (pintype "passive"))
      (node (ref "D13") (pin "50") (pinfunction "CLK-_50") (pintype "input"))
    )
    (net (code "76") (name "Net-(D13B-RBIAS)") (class "Default")
      (node (ref "D13") (pin "42") (pinfunction "RBIAS_42") (pintype "input"))
      (node (ref "R95") (pin "1") (pinfunction "1_1") (pintype "passive"))
    )
    (net (code "77") (name "Net-(D13B-SENSE)") (class "Default")
      (node (ref "D13") (pin "40") (pinfunction "SENSE_40") (pintype "input"))
      (node (ref "R88") (pin "2") (pinfunction "2_2") (pintype "passive"))
      (node (ref "R93") (pin "1") (pinfunction "1_1") (pintype "passive"))
    )
    (net (code "78") (name "Net-(D14-VOUTA)") (class "Default")
      (node (ref "D14") (pin "5") (pinfunction "VOUTA_5") (pintype "tri_state"))
      (node (ref "X6") (pin "1") (pinfunction "Left_1") (pintype "passive"))
    )
    (net (code "79") (name "Net-(D14-VOUTB)") (class "Default")
      (node (ref "D14") (pin "6") (pinfunction "VOUTB_6") (pintype "tri_state"))
      (node (ref "X6") (pin "3") (pinfunction "Rigth_3") (pintype "passive"))
    )
    (net (code "80") (name "Net-(D14-VREFA)") (class "Default")
      (node (ref "C219") (pin "2") (pinfunction "2_2") (pintype "passive"))
      (node (ref "D14") (pin "3") (pinfunction "VREFB_3") (pintype "input"))
      (node (ref "D14") (pin "4") (pinfunction "VREFA_4") (pintype "input"))
      (node (ref "R91") (pin "1") (pinfunction "1_1") (pintype "passive"))
      (node (ref "R92") (pin "1") (pinfunction "1_1") (pintype "passive"))
    )
    (net (code "81") (name "Net-(D15A-BYPASS)") (class "Default")
      (node (ref "C245") (pin "2") (pinfunction "2_2") (pintype "passive"))
      (node (ref "D15") (pin "9") (pinfunction "BYPASS_9") (pintype "passive"))
    )
    (net (code "82") (name "Net-(D15A-CP)") (class "Default")
      (node (ref "C247") (pin "2") (pinfunction "2_2") (pintype "passive"))
      (node (ref "D15") (pin "4") (pinfunction "CP_4") (pintype "output"))
      (node (ref "D15") (pin "8") (pinfunction "LF_8") (pintype "input"))
      (node (ref "R107") (pin "1") (pinfunction "1_1") (pintype "passive"))
    )
    (net (code "83") (name "Net-(D15A-CPRSET)") (class "Default")
      (node (ref "D15") (pin "46") (pinfunction "CPRSET_46") (pintype "input"))
      (node (ref "R106") (pin "1") (pinfunction "1_1") (pintype "passive"))
    )
    (net (code "84") (name "Net-(D15A-RSET)") (class "Default")
      (node (ref "D15") (pin "44") (pinfunction "RSET_44") (pintype "input"))
      (node (ref "R105") (pin "1") (pinfunction "1_1") (pintype "passive"))
    )
    (net (code "85") (name "Net-(D15A-~{CLK})") (class "Default")
      (node (ref "C236") (pin "2") (pinfunction "2_2") (pintype "passive"))
      (node (ref "D15") (pin "12") (pinfunction "~{CLK}_12") (pintype "input"))
    )
    (net (code "86") (name "Net-(D15B-VCP)") (class "Default")
      (node (ref "C243") (pin "2") (pinfunction "2_2") (pintype "passive"))
      (node (ref "C244") (pin "2") (pinfunction "2_2") (pintype "passive"))
      (node (ref "D15") (pin "3") (pinfunction "VCP_3") (pintype "power_in"))
      (node (ref "L16") (pin "1") (pinfunction "1_1") (pintype "passive"))
    )
    (net (code "87") (name "Net-(R85-Pad2)") (class "Default")
      (node (ref "R85") (pin "2") (pinfunction "2_2") (pintype "passive"))
      (node (ref "T1") (pin "1") (pinfunction "1_1") (pintype "passive"))
    )
    (net (code "88") (name "Net-(R89-Pad2)") (class "Default")
      (node (ref "R89") (pin "2") (pinfunction "2_2") (pintype "passive"))
      (node (ref "T1") (pin "3") (pinfunction "3_3") (pintype "passive"))
    )
    (net (code "89") (name "Net-(R96-Pad2)") (class "Default")
      (node (ref "R96") (pin "2") (pinfunction "2_2") (pintype "passive"))
      (node (ref "T2") (pin "3") (pinfunction "3_3") (pintype "passive"))
    )
    (net (code "90") (name "Net-(R100-Pad2)") (class "Default")
      (node (ref "R100") (pin "2") (pinfunction "2_2") (pintype "passive"))
      (node (ref "T2") (pin "1") (pinfunction "1_1") (pintype "passive"))
    )
    (net (code "91") (name "Net-(VG2-EN)") (class "Default")
      (node (ref "R102") (pin "2") (pinfunction "2_2") (pintype "passive"))
      (node (ref "VG2") (pin "1") (pinfunction "EN_1") (pintype "passive"))
    )
    (net (code "92") (name "unconnected-(D13A-D0B_(LSB)¦FD2--Pad58)") (class "Default")
      (node (ref "D13") (pin "58") (pinfunction "D0B_(LSB)¦FD2-_58") (pintype "tri_state"))
    )
    (net (code "93") (name "unconnected-(D13A-D1B¦FD2+-Pad59)") (class "Default")
      (node (ref "D13") (pin "59") (pinfunction "D1B¦FD2+_59") (pintype "tri_state"))
    )
    (net (code "94") (name "unconnected-(D13A-D2B¦FD3--Pad60)") (class "Default")
      (node (ref "D13") (pin "60") (pinfunction "D2B¦FD3-_60") (pintype "tri_state"))
    )
    (net (code "95") (name "unconnected-(D13A-D3B¦FD3+-Pad61)") (class "Default")
      (node (ref "D13") (pin "61") (pinfunction "D3B¦FD3+_61") (pintype "tri_state"))
    )
    (net (code "96") (name "unconnected-(D13A-FD0B¦FD0--Pad53)") (class "Default")
      (node (ref "D13") (pin "53") (pinfunction "FD0B¦FD0-_53") (pintype "output"))
    )
    (net (code "97") (name "unconnected-(D13A-FD1B¦FD0+-Pad54)") (class "Default")
      (node (ref "D13") (pin "54") (pinfunction "FD1B¦FD0+_54") (pintype "output"))
    )
    (net (code "98") (name "unconnected-(D13A-FD2B¦FD1--Pad55)") (class "Default")
      (node (ref "D13") (pin "55") (pinfunction "FD2B¦FD1-_55") (pintype "output"))
    )
    (net (code "99") (name "unconnected-(D13A-FD3B¦FD1+-Pad56)") (class "Default")
      (node (ref "D13") (pin "56") (pinfunction "FD3B¦FD1+_56") (pintype "output"))
    )
    (net (code "100") (name "unconnected-(D13B-SMI_SCLK{slash}PDWN-Pad34)") (class "Default")
      (node (ref "D13") (pin "34") (pinfunction "SMI_SCLK/PDWN_34") (pintype "bidirectional"))
    )
    (net (code "101") (name "unconnected-(D13B-SMI_SDFS-Pad35)") (class "Default")
      (node (ref "D13") (pin "35") (pinfunction "SMI_SDFS_35") (pintype "output"))
    )
    (net (code "102") (name "unconnected-(D13B-SMI_SDO{slash}OEB-Pad33)") (class "Default")
      (node (ref "D13") (pin "33") (pinfunction "SMI_SDO/OEB_33") (pintype "bidirectional"))
    )
    (net (code "103") (name "unconnected-(D15A-CLK-Pad11)") (class "Default")
      (node (ref "D15") (pin "11") (pinfunction "CLK_11") (pintype "input"))
    )
    (net (code "104") (name "unconnected-(D15A-LD-Pad2)") (class "Default")
      (node (ref "D15") (pin "2") (pinfunction "LD_2") (pintype "output"))
    )
    (net (code "105") (name "unconnected-(D15A-OUT0-Pad42)") (class "Default")
      (node (ref "D15") (pin "42") (pinfunction "OUT0_42") (pintype "output"))
    )
    (net (code "106") (name "unconnected-(D15A-OUT1-Pad39)") (class "Default")
      (node (ref "D15") (pin "39") (pinfunction "OUT1_39") (pintype "output"))
    )
    (net (code "107") (name "unconnected-(D15A-OUT2-Pad19)") (class "Default")
      (node (ref "D15") (pin "19") (pinfunction "OUT2_19") (pintype "output"))
    )
    (net (code "108") (name "unconnected-(D15A-OUT3-Pad22)") (class "Default")
      (node (ref "D15") (pin "22") (pinfunction "OUT3_22") (pintype "output"))
    )
    (net (code "109") (name "unconnected-(D15A-OUT5(OUT5A)-Pad33)") (class "Default")
      (node (ref "D15") (pin "33") (pinfunction "OUT5(OUT5A)_33") (pintype "output"))
    )
    (net (code "110") (name "unconnected-(D15A-OUT6(OUT6A)-Pad26)") (class "Default")
      (node (ref "D15") (pin "26") (pinfunction "OUT6(OUT6A)_26") (pintype "output"))
    )
    (net (code "111") (name "unconnected-(D15A-OUT7(OUT7A)-Pad28)") (class "Default")
      (node (ref "D15") (pin "28") (pinfunction "OUT7(OUT7A)_28") (pintype "output"))
    )
    (net (code "112") (name "unconnected-(D15A-~{OUT0}-Pad41)") (class "Default")
      (node (ref "D15") (pin "41") (pinfunction "~{OUT0}_41") (pintype "output"))
    )
    (net (code "113") (name "unconnected-(D15A-~{OUT1}-Pad38)") (class "Default")
      (node (ref "D15") (pin "38") (pinfunction "~{OUT1}_38") (pintype "output"))
    )
    (net (code "114") (name "unconnected-(D15A-~{OUT2}-Pad20)") (class "Default")
      (node (ref "D15") (pin "20") (pinfunction "~{OUT2}_20") (pintype "output"))
    )
    (net (code "115") (name "unconnected-(D15A-~{OUT3}-Pad23)") (class "Default")
      (node (ref "D15") (pin "23") (pinfunction "~{OUT3}_23") (pintype "output"))
    )
    (net (code "116") (name "unconnected-(D15A-~{OUT5}(OUT5B)-Pad32)") (class "Default")
      (node (ref "D15") (pin "32") (pinfunction "~{OUT5}(OUT5B)_32") (pintype "output"))
    )
    (net (code "117") (name "unconnected-(D15A-~{OUT6}(OUT6B)-Pad27)") (class "Default")
      (node (ref "D15") (pin "27") (pinfunction "~{OUT6}(OUT6B)_27") (pintype "output"))
    )
    (net (code "118") (name "unconnected-(D15A-~{OUT7}(OUT7B)-Pad29)") (class "Default")
      (node (ref "D15") (pin "29") (pinfunction "~{OUT7}(OUT7B)_29") (pintype "output"))
    )
    (net (code "119") (name "unconnected-(D15A-~{PD}-Pad18)") (class "Default")
      (node (ref "D15") (pin "18") (pinfunction "~{PD}_18") (pintype "input"))
    )
    (net (code "120") (name "unconnected-(D15A-~{RESET}-Pad17)") (class "Default")
      (node (ref "D15") (pin "17") (pinfunction "~{RESET}_17") (pintype "input"))
    )
    (net (code "121") (name "unconnected-(D15A-~{SYNC}-Pad7)") (class "Default")
      (node (ref "D15") (pin "7") (pinfunction "~{SYNC}_7") (pintype "input"))
    )
    (net (code "122") (name "unconnected-(T1-Pad5)") (class "Default")
      (node (ref "T1") (pin "5") (pinfunction "5_5") (pintype "passive"))
    )
    (net (code "123") (name "unconnected-(T2-Pad5)") (class "Default")
      (node (ref "T2") (pin "5") (pinfunction "5_5") (pintype "passive"))
    )
  )
)
